# CRSC0005.net
KiCad netlist of a schematic drawn in Altium Designer
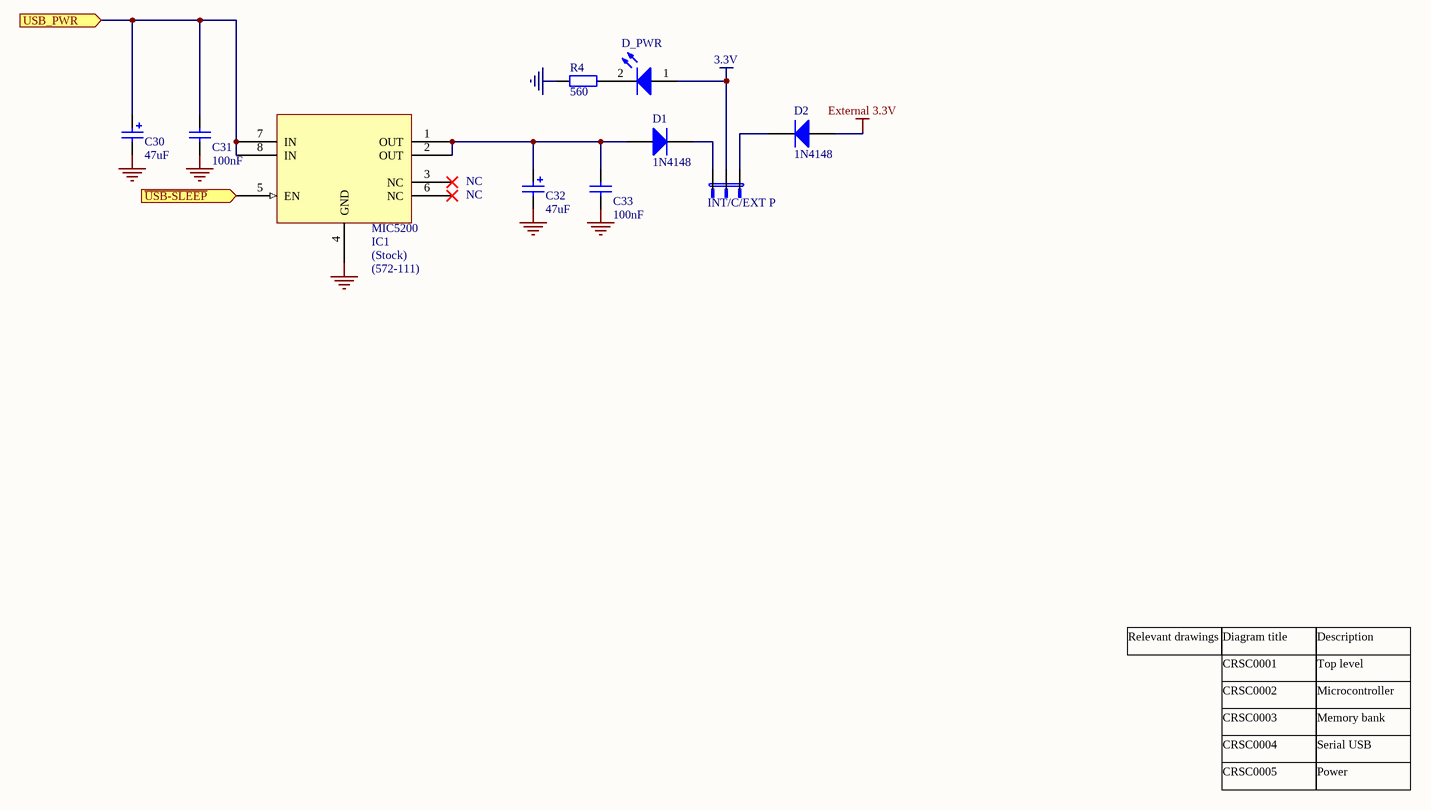
[diagram p0: CRSC0005.SchDoc]

(export (version "E")
  (design (tool "Eeschema 10.0.6"))
  (components
    (comp (ref "C30")
      (value "47uF")
      (footprint "SMDD_E")
      (description "Polarized Capacitor (Surface Mount)")
      (fields
        (field (name "MANUFACTURER") "Generic Components")
        (field (name "Comment") "Cap Pol3")
        (field (name "PUBLISHER") "Altium Hobart Technology Centre")
      )
      (libsource (lib "Miscellaneous Devices") (part "Cap Pol3"))
    )
    (comp (ref "C31")
      (value "100nF")
      (footprint "0805")
      (description "Capacitor (Semiconductor SIM Model)")
      (fields
        (field (name "MANUFACTURER") "Generic Components")
        (field (name "Comment") "Cap Semi")
        (field (name "PUBLISHER") "Altium Hobart Technology Centre")
      )
      (libsource (lib "Miscellaneous Devices") (part "Cap Semi"))
    )
    (comp (ref "C32")
      (value "47uF")
      (footprint "smdd_e")
      (description "Polarized Capacitor (Surface Mount)")
      (fields
        (field (name "MANUFACTURER") "Generic Components")
        (field (name "Comment") "Cap Pol3")
        (field (name "PUBLISHER") "Altium Hobart Technology Centre")
      )
      (libsource (lib "Miscellaneous Devices") (part "Cap Pol3"))
    )
    (comp (ref "C33")
      (value "100nF")
      (footprint "0805")
      (description "Capacitor (Semiconductor SIM Model)")
      (fields
        (field (name "MANUFACTURER") "Generic Components")
        (field (name "Comment") "Cap Semi")
        (field (name "PUBLISHER") "Altium Hobart Technology Centre")
      )
      (libsource (lib "Miscellaneous Devices") (part "Cap Semi"))
    )
    (comp (ref "D1")
      (value "1N4148")
      (footprint "SOD123")
      (description "High Conductance Fast Diode")
      (fields (field (name "PUBLISHER") "Altium Limited"))
      (libsource (lib "SELF-MADE_2905") (part "1N4148"))
    )
    (comp (ref "D2")
      (value "1N4148")
      (footprint "SOD123")
      (description "High Conductance Fast Diode")
      (fields (field (name "PUBLISHER") "Altium Limited"))
      (libsource (lib "SELF-MADE_2905") (part "1N4148"))
    )
    (comp (ref "D_PWR")
      (value "LED")
      (footprint "0805")
      (description "Typical INFRARED GaAs LED")
      (fields
        (field (name "MANUFACTURER") "Generic Components")
        (field (name "PUBLISHER") "Altium Hobart Technology Centre")
      )
      (libsource (lib "SELF-MADE_1004") (part "LED0"))
    )
    (comp (ref "IC1")
      (value "MIC5200")
      (footprint "MIC5200-3.3BM")
      (description "MIC5200-3.3BM 3.3V 100mA LDO Voltage Regulator")
      (libsource (lib "Components") (part "MIC5200"))
    )
    (comp (ref "INT/C/EXT P")
      (value "3pins jumper")
      (footprint "JUMPER3pins")
      (libsource (lib "SELF-MADE_2905") (part "3pins jumper"))
    )
    (comp (ref "R4")
      (value "560")
      (footprint "0805")
      (description "Resistor")
      (fields
        (field (name "MANUFACTURER") "Generic Components")
        (field (name "PUBLISHER") "Altium Hobart Technology Centre")
      )
      (libsource (lib "SELF-MADE_1004") (part "Res2"))
    )
  )
  (nets
    (net (code "1") (name "/USB-SLEEP") (class "Default")
      (node (ref "IC1") (pin "5") (pinfunction "EN_5") (pintype "input"))
    )
    (net (code "2") (name "/USB_PWR") (class "Default")
      (node (ref "C30") (pin "1") (pinfunction "1_1") (pintype "passive"))
      (node (ref "C31") (pin "1") (pinfunction "1_1") (pintype "passive"))
      (node (ref "IC1") (pin "7") (pinfunction "IN_7") (pintype "power_in"))
      (node (ref "IC1") (pin "8") (pinfunction "IN_8") (pintype "power_in"))
    )
    (net (code "3") (name "3.3V") (class "Default")
      (node (ref "D_PWR") (pin "1") (pinfunction "A_1") (pintype "passive"))
      (node (ref "INT/C/EXT P") (pin "2") (pinfunction "2_2") (pintype "passive"))
    )
    (net (code "4") (name "External 3.3V") (class "Default")
      (node (ref "D2") (pin "1") (pinfunction "A_1") (pintype "passive"))
    )
    (net (code "5") (name "GND") (class "Default")
      (node (ref "C30") (pin "2") (pinfunction "2_2") (pintype "passive"))
      (node (ref "C31") (pin "2") (pinfunction "2_2") (pintype "passive"))
      (node (ref "C32") (pin "2") (pinfunction "2_2") (pintype "passive"))
      (node (ref "C33") (pin "2") (pinfunction "2_2") (pintype "passive"))
      (node (ref "IC1") (pin "4") (pinfunction "GND_4") (pintype "power_in"))
      (node (ref "R4") (pin "1") (pinfunction "1_1") (pintype "passive"))
    )
    (net (code "6") (name "Net-(D1-A)") (class "Default")
      (node (ref "C32") (pin "1") (pinfunction "1_1") (pintype "passive"))
      (node (ref "C33") (pin "1") (pinfunction "1_1") (pintype "passive"))
      (node (ref "D1") (pin "1") (pinfunction "A_1") (pintype "passive"))
      (node (ref "IC1") (pin "1") (pinfunction "OUT_1") (pintype "power_in"))
      (node (ref "IC1") (pin "2") (pinfunction "OUT_2") (pintype "power_in"))
    )
    (net (code "7") (name "Net-(D1-K)") (class "Default")
      (node (ref "D1") (pin "2") (pinfunction "K_2") (pintype "passive"))
      (node (ref "INT/C/EXT P") (pin "1") (pinfunction "1_1") (pintype "passive"))
    )
    (net (code "8") (name "Net-(D2-K)") (class "Default")
      (node (ref "D2") (pin "2") (pinfunction "K_2") (pintype "passive"))
      (node (ref "INT/C/EXT P") (pin "3") (pinfunction "3_3") (pintype "passive"))
    )
    (net (code "9") (name "Net-(D_PWR-K)") (class "Default")
      (node (ref "D_PWR") (pin "2") (pinfunction "K_2") (pintype "passive"))
      (node (ref "R4") (pin "2") (pinfunction "2_2") (pintype "passive"))
    )
    (net (code "10") (name "unconnected-(IC1-NC-Pad3)") (class "Default")
      (node (ref "IC1") (pin "3") (pinfunction "NC_3") (pintype "passive+no_connect"))
    )
    (net (code "11") (name "unconnected-(IC1-NC-Pad6)") (class "Default")
      (node (ref "IC1") (pin "6") (pinfunction "NC_6") (pintype "passive+no_connect"))
    )
  )
)
